# AD7606.net
KiCad netlist of a schematic drawn in Altium Designer
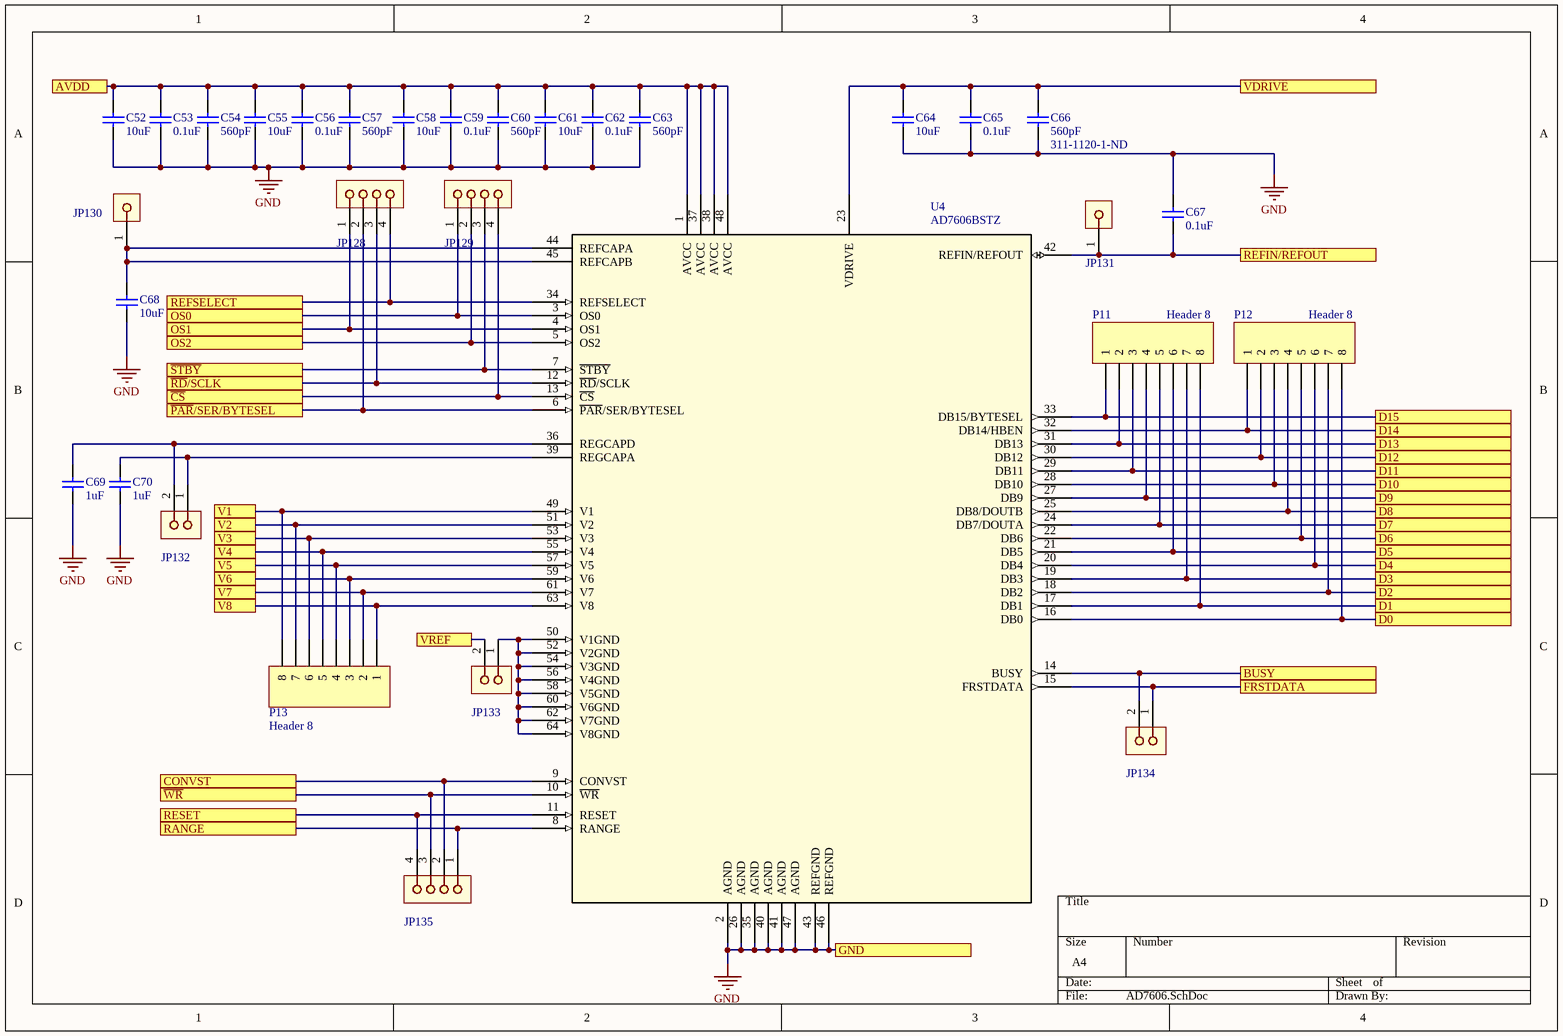
[diagram p0: AD7606.SchDoc]

(export (version "E")
  (design (tool "Eeschema 10.0.6"))
  (components
    (comp (ref "C52")
      (value "10uF")
      (footprint "CLS_Library:C0805")
      (description "Cap 10uF")
      (fields
        (field (name "MANUFACTURER") "Taiyo Yuden")
        (field (name "MANUFACTURER PART NUMBER") "UMK212SD103KD-T")
      )
      (libsource (lib "Chip1_TestBoard") (part "Cap 10uF"))
    )
    (comp (ref "C53")
      (value "0.1uF")
      (footprint "CLS_Library:C0805")
      (description "Cap 0.1uF")
      (fields
        (field (name "MANUFACTURER") "Taiyo Yuden")
        (field (name "MANUFACTURER PART NUMBER") "UMK212SD103KD-T")
      )
      (libsource (lib "Chip1_TestBoard") (part "Cap 0.1uF"))
    )
    (comp (ref "C54")
      (value "560pF")
      (footprint "CLS_Library:C0805")
      (description "Cap 560pF")
      (fields
        (field (name "MANUFACTURER") "Taiyo Yuden")
        (field (name "MANUFACTURER PART NUMBER") "UMK212SD103KD-T")
      )
      (libsource (lib "Chip1_TestBoard") (part "Cap 560pF"))
    )
    (comp (ref "C55")
      (value "10uF")
      (footprint "CLS_Library:C0805")
      (description "Cap 10uF")
      (fields
        (field (name "MANUFACTURER") "Taiyo Yuden")
        (field (name "MANUFACTURER PART NUMBER") "UMK212SD103KD-T")
      )
      (libsource (lib "Chip1_TestBoard") (part "Cap 10uF"))
    )
    (comp (ref "C56")
      (value "0.1uF")
      (footprint "CLS_Library:C0805")
      (description "Cap 0.1uF")
      (fields
        (field (name "MANUFACTURER") "Taiyo Yuden")
        (field (name "MANUFACTURER PART NUMBER") "UMK212SD103KD-T")
      )
      (libsource (lib "Chip1_TestBoard") (part "Cap 0.1uF"))
    )
    (comp (ref "C57")
      (value "560pF")
      (footprint "CLS_Library:C0805")
      (description "Cap 560pF")
      (fields
        (field (name "MANUFACTURER") "Taiyo Yuden")
        (field (name "MANUFACTURER PART NUMBER") "UMK212SD103KD-T")
      )
      (libsource (lib "Chip1_TestBoard") (part "Cap 560pF"))
    )
    (comp (ref "C58")
      (value "10uF")
      (footprint "CLS_Library:C0805")
      (description "Cap 10uF")
      (fields
        (field (name "MANUFACTURER") "Taiyo Yuden")
        (field (name "MANUFACTURER PART NUMBER") "UMK212SD103KD-T")
      )
      (libsource (lib "Chip1_TestBoard") (part "Cap 10uF"))
    )
    (comp (ref "C59")
      (value "0.1uF")
      (footprint "CLS_Library:C0805")
      (description "Cap 0.1uF")
      (fields
        (field (name "MANUFACTURER") "Taiyo Yuden")
        (field (name "MANUFACTURER PART NUMBER") "UMK212SD103KD-T")
      )
      (libsource (lib "Chip1_TestBoard") (part "Cap 0.1uF"))
    )
    (comp (ref "C60")
      (value "560pF")
      (footprint "CLS_Library:C0805")
      (description "Cap 560pF")
      (fields
        (field (name "MANUFACTURER") "Taiyo Yuden")
        (field (name "MANUFACTURER PART NUMBER") "UMK212SD103KD-T")
      )
      (libsource (lib "Chip1_TestBoard") (part "Cap 560pF"))
    )
    (comp (ref "C61")
      (value "10uF")
      (footprint "CLS_Library:C0805")
      (description "Cap 10uF")
      (fields
        (field (name "MANUFACTURER") "Taiyo Yuden")
        (field (name "MANUFACTURER PART NUMBER") "UMK212SD103KD-T")
      )
      (libsource (lib "Chip1_TestBoard") (part "Cap 10uF"))
    )
    (comp (ref "C62")
      (value "0.1uF")
      (footprint "CLS_Library:C0805")
      (description "Cap 0.1uF")
      (fields
        (field (name "MANUFACTURER") "Taiyo Yuden")
        (field (name "MANUFACTURER PART NUMBER") "UMK212SD103KD-T")
      )
      (libsource (lib "Chip1_TestBoard") (part "Cap 0.1uF"))
    )
    (comp (ref "C63")
      (value "560pF")
      (footprint "CLS_Library:C0805")
      (description "Cap 560pF")
      (fields
        (field (name "MANUFACTURER") "Taiyo Yuden")
        (field (name "MANUFACTURER PART NUMBER") "UMK212SD103KD-T")
      )
      (libsource (lib "Chip1_TestBoard") (part "Cap 560pF"))
    )
    (comp (ref "C64")
      (value "10uF")
      (footprint "CLS_Library:C0805")
      (description "Cap 10uF")
      (fields
        (field (name "MANUFACTURER") "Taiyo Yuden")
        (field (name "MANUFACTURER PART NUMBER") "UMK212SD103KD-T")
      )
      (libsource (lib "Chip1_TestBoard") (part "Cap 10uF"))
    )
    (comp (ref "C65")
      (value "0.1uF")
      (footprint "CLS_Library:C0805")
      (description "Cap 0.1uF")
      (fields
        (field (name "MANUFACTURER") "Taiyo Yuden")
        (field (name "MANUFACTURER PART NUMBER") "UMK212SD103KD-T")
      )
      (libsource (lib "Chip1_TestBoard") (part "Cap 0.1uF"))
    )
    (comp (ref "C66")
      (value "560pF")
      (footprint "CLS_Library:C0805")
      (description "Cap 560pF")
      (fields
        (field (name "MANUFACTURER") "Taiyo Yuden")
        (field (name "MANUFACTURER PART NUMBER") "UMK212SD103KD-T")
        (field (name "SUPPLIER PART NUMBER 1") "311-1120-1-ND")
      )
      (libsource (lib "Chip1_TestBoard") (part "Cap 560pF"))
    )
    (comp (ref "C67")
      (value "0.1uF")
      (footprint "CLS_Library:C0805")
      (description "Cap 0.1uF")
      (fields
        (field (name "MANUFACTURER") "Taiyo Yuden")
        (field (name "MANUFACTURER PART NUMBER") "UMK212SD103KD-T")
      )
      (libsource (lib "Chip1_TestBoard") (part "Cap 0.1uF"))
    )
    (comp (ref "C68")
      (value "10uF")
      (footprint "CLS_Library:C0805")
      (description "Cap 10uF")
      (fields
        (field (name "MANUFACTURER") "Taiyo Yuden")
        (field (name "MANUFACTURER PART NUMBER") "UMK212SD103KD-T")
      )
      (libsource (lib "Chip1_TestBoard") (part "Cap 10uF"))
    )
    (comp (ref "C69")
      (value "1uF")
      (footprint "CLS_Library:C0805")
      (description "Cap 1uF")
      (fields
        (field (name "MANUFACTURER") "Taiyo Yuden")
        (field (name "MANUFACTURER PART NUMBER") "UMK212SD103KD-T")
      )
      (libsource (lib "Chip1_TestBoard") (part "Cap 1uF"))
    )
    (comp (ref "C70")
      (value "1uF")
      (footprint "CLS_Library:C0805")
      (description "Cap 1uF")
      (fields
        (field (name "MANUFACTURER") "Taiyo Yuden")
        (field (name "MANUFACTURER PART NUMBER") "UMK212SD103KD-T")
      )
      (libsource (lib "Chip1_TestBoard") (part "Cap 1uF"))
    )
    (comp (ref "JP128")
      (value "01x04")
      (footprint "01x04_0.1in_th_straight_b_nom")
      (description "01X04 generic terminal connector")
      (libsource (lib "Chip1_TestBoard") (part "01x04"))
    )
    (comp (ref "JP129")
      (value "01x04")
      (footprint "01x04_0.1in_th_straight_b_nom")
      (description "01X04 generic terminal connector")
      (libsource (lib "Chip1_TestBoard") (part "01x04"))
    )
    (comp (ref "JP130")
      (value "01x01")
      (footprint "01x01_0_0.1in_th_straight_b_nom")
      (description "01X01 generic terminal connector")
      (libsource (lib "Chip1_TestBoard") (part "01x01"))
    )
    (comp (ref "JP131")
      (value "01x01")
      (footprint "01x01_0_0.1in_th_straight_b_nom")
      (description "01X01 generic terminal connector")
      (libsource (lib "Chip1_TestBoard") (part "01x01"))
    )
    (comp (ref "JP132")
      (value "01x02")
      (footprint "01x02_0.1in_th_straight_b_nom")
      (description "01X02 generic terminal connector")
      (libsource (lib "Chip1_TestBoard") (part "01x02"))
    )
    (comp (ref "JP133")
      (value "01x02")
      (footprint "01x02_0.1in_th_straight_b_nom")
      (description "01X02 generic terminal connector")
      (libsource (lib "Chip1_TestBoard") (part "01x02"))
    )
    (comp (ref "JP134")
      (value "01x02")
      (footprint "01x02_0.1in_th_straight_b_nom")
      (description "01X02 generic terminal connector")
      (libsource (lib "Chip1_TestBoard") (part "01x02"))
    )
    (comp (ref "JP135")
      (value "01x04")
      (footprint "01x04_0.1in_th_straight_b_nom")
      (description "01X04 generic terminal connector")
      (libsource (lib "") (part "01x04_1"))
    )
    (comp (ref "P11")
      (value "Header 8")
      (footprint "HDR1X8")
      (description "Header, 8-Pin")
      (fields (field (name "PUBLISHER") "Altium Limited"))
      (libsource (lib "Miscellaneous Connectors") (part "Header 8"))
    )
    (comp (ref "P12")
      (value "Header 8")
      (footprint "HDR1X8")
      (description "Header, 8-Pin")
      (fields (field (name "PUBLISHER") "Altium Limited"))
      (libsource (lib "Miscellaneous Connectors") (part "Header 8"))
    )
    (comp (ref "P13")
      (value "Header 8")
      (footprint "HDR1X8")
      (description "Header, 8-Pin")
      (fields (field (name "PUBLISHER") "Altium Limited"))
      (libsource (lib "") (part "Header 8_1"))
    )
    (comp (ref "U4")
      (value "AD7606BSTZ")
      (footprint "AD7606BSTZ")
      (description "No Description Available")
      (fields (field (name "COPYRIGHT") "Copyright (C) 2018 Accelerated Designs. All rights reserved"))
      (libsource (lib "Chip1_TestBoard") (part "AD7606BSTZ"))
    )
  )
  (nets
    (net (code "1") (name "/AVDD") (class "Default")
      (node (ref "C52") (pin "2") (pinfunction "2_2") (pintype "passive"))
      (node (ref "C53") (pin "2") (pinfunction "2_2") (pintype "passive"))
      (node (ref "C54") (pin "2") (pinfunction "2_2") (pintype "passive"))
      (node (ref "C55") (pin "2") (pinfunction "2_2") (pintype "passive"))
      (node (ref "C56") (pin "2") (pinfunction "2_2") (pintype "passive"))
      (node (ref "C57") (pin "2") (pinfunction "2_2") (pintype "passive"))
      (node (ref "C58") (pin "2") (pinfunction "2_2") (pintype "passive"))
      (node (ref "C59") (pin "2") (pinfunction "2_2") (pintype "passive"))
      (node (ref "C60") (pin "2") (pinfunction "2_2") (pintype "passive"))
      (node (ref "C61") (pin "2") (pinfunction "2_2") (pintype "passive"))
      (node (ref "C62") (pin "2") (pinfunction "2_2") (pintype "passive"))
      (node (ref "C63") (pin "2") (pinfunction "2_2") (pintype "passive"))
      (node (ref "U4") (pin "1") (pinfunction "AVCC_1") (pintype "power_in"))
      (node (ref "U4") (pin "37") (pinfunction "AVCC_37") (pintype "power_in"))
      (node (ref "U4") (pin "38") (pinfunction "AVCC_38") (pintype "power_in"))
      (node (ref "U4") (pin "48") (pinfunction "AVCC_48") (pintype "power_in"))
    )
    (net (code "2") (name "/BUSY") (class "Default")
      (node (ref "JP134") (pin "2") (pinfunction "2_2") (pintype "passive"))
      (node (ref "U4") (pin "14") (pinfunction "BUSY_14") (pintype "output"))
    )
    (net (code "3") (name "/CONVST") (class "Default")
      (node (ref "JP135") (pin "2") (pinfunction "2_2") (pintype "passive"))
      (node (ref "U4") (pin "9") (pinfunction "CONVST_9") (pintype "input"))
    )
    (net (code "4") (name "/D0") (class "Default")
      (node (ref "P12") (pin "8") (pinfunction "8_8") (pintype "passive"))
      (node (ref "U4") (pin "16") (pinfunction "DB0_16") (pintype "output"))
    )
    (net (code "5") (name "/D1") (class "Default")
      (node (ref "P11") (pin "8") (pinfunction "8_8") (pintype "passive"))
      (node (ref "U4") (pin "17") (pinfunction "DB1_17") (pintype "output"))
    )
    (net (code "6") (name "/D2") (class "Default")
      (node (ref "P12") (pin "7") (pinfunction "7_7") (pintype "passive"))
      (node (ref "U4") (pin "18") (pinfunction "DB2_18") (pintype "output"))
    )
    (net (code "7") (name "/D3") (class "Default")
      (node (ref "P11") (pin "7") (pinfunction "7_7") (pintype "passive"))
      (node (ref "U4") (pin "19") (pinfunction "DB3_19") (pintype "output"))
    )
    (net (code "8") (name "/D4") (class "Default")
      (node (ref "P12") (pin "6") (pinfunction "6_6") (pintype "passive"))
      (node (ref "U4") (pin "20") (pinfunction "DB4_20") (pintype "output"))
    )
    (net (code "9") (name "/D5") (class "Default")
      (node (ref "P11") (pin "6") (pinfunction "6_6") (pintype "passive"))
      (node (ref "U4") (pin "21") (pinfunction "DB5_21") (pintype "output"))
    )
    (net (code "10") (name "/D6") (class "Default")
      (node (ref "P12") (pin "5") (pinfunction "5_5") (pintype "passive"))
      (node (ref "U4") (pin "22") (pinfunction "DB6_22") (pintype "output"))
    )
    (net (code "11") (name "/D7") (class "Default")
      (node (ref "P11") (pin "5") (pinfunction "5_5") (pintype "passive"))
      (node (ref "U4") (pin "24") (pinfunction "DB7/DOUTA_24") (pintype "output"))
    )
    (net (code "12") (name "/D8") (class "Default")
      (node (ref "P12") (pin "4") (pinfunction "4_4") (pintype "passive"))
      (node (ref "U4") (pin "25") (pinfunction "DB8/DOUTB_25") (pintype "output"))
    )
    (net (code "13") (name "/D9") (class "Default")
      (node (ref "P11") (pin "4") (pinfunction "4_4") (pintype "passive"))
      (node (ref "U4") (pin "27") (pinfunction "DB9_27") (pintype "output"))
    )
    (net (code "14") (name "/D10") (class "Default")
      (node (ref "P12") (pin "3") (pinfunction "3_3") (pintype "passive"))
      (node (ref "U4") (pin "28") (pinfunction "DB10_28") (pintype "output"))
    )
    (net (code "15") (name "/D11") (class "Default")
      (node (ref "P11") (pin "3") (pinfunction "3_3") (pintype "passive"))
      (node (ref "U4") (pin "29") (pinfunction "DB11_29") (pintype "output"))
    )
    (net (code "16") (name "/D12") (class "Default")
      (node (ref "P12") (pin "2") (pinfunction "2_2") (pintype "passive"))
      (node (ref "U4") (pin "30") (pinfunction "DB12_30") (pintype "output"))
    )
    (net (code "17") (name "/D13") (class "Default")
      (node (ref "P11") (pin "2") (pinfunction "2_2") (pintype "passive"))
      (node (ref "U4") (pin "31") (pinfunction "DB13_31") (pintype "output"))
    )
    (net (code "18") (name "/D14") (class "Default")
      (node (ref "P12") (pin "1") (pinfunction "1_1") (pintype "passive"))
      (node (ref "U4") (pin "32") (pinfunction "DB14/HBEN_32") (pintype "output"))
    )
    (net (code "19") (name "/D15") (class "Default")
      (node (ref "P11") (pin "1") (pinfunction "1_1") (pintype "passive"))
      (node (ref "U4") (pin "33") (pinfunction "DB15/BYTESEL_33") (pintype "output"))
    )
    (net (code "20") (name "/FRSTDATA") (class "Default")
      (node (ref "JP134") (pin "1") (pinfunction "1_1") (pintype "passive"))
      (node (ref "U4") (pin "15") (pinfunction "FRSTDATA_15") (pintype "output"))
    )
    (net (code "21") (name "/OS0") (class "Default")
      (node (ref "JP129") (pin "1") (pinfunction "1_1") (pintype "passive"))
      (node (ref "U4") (pin "3") (pinfunction "OS0_3") (pintype "input"))
    )
    (net (code "22") (name "/OS1") (class "Default")
      (node (ref "JP128") (pin "1") (pinfunction "1_1") (pintype "passive"))
      (node (ref "U4") (pin "4") (pinfunction "OS1_4") (pintype "input"))
    )
    (net (code "23") (name "/OS2") (class "Default")
      (node (ref "JP129") (pin "2") (pinfunction "2_2") (pintype "passive"))
      (node (ref "U4") (pin "5") (pinfunction "OS2_5") (pintype "input"))
    )
    (net (code "24") (name "/RANGE") (class "Default")
      (node (ref "JP135") (pin "1") (pinfunction "1_1") (pintype "passive"))
      (node (ref "U4") (pin "8") (pinfunction "RANGE_8") (pintype "input"))
    )
    (net (code "25") (name "/REFIN{slash}REFOUT") (class "Default")
      (node (ref "C67") (pin "1") (pinfunction "1_1") (pintype "passive"))
      (node (ref "JP131") (pin "1") (pinfunction "1_1") (pintype "passive"))
      (node (ref "U4") (pin "42") (pinfunction "REFIN/REFOUT_42") (pintype "bidirectional"))
    )
    (net (code "26") (name "/REFSELECT") (class "Default")
      (node (ref "JP128") (pin "4") (pinfunction "4_4") (pintype "passive"))
      (node (ref "U4") (pin "34") (pinfunction "REFSELECT_34") (pintype "input"))
    )
    (net (code "27") (name "/RESET") (class "Default")
      (node (ref "JP135") (pin "4") (pinfunction "4_4") (pintype "passive"))
      (node (ref "U4") (pin "11") (pinfunction "RESET_11") (pintype "input"))
    )
    (net (code "28") (name "/V1") (class "Default")
      (node (ref "P13") (pin "8") (pinfunction "8_8") (pintype "passive"))
      (node (ref "U4") (pin "49") (pinfunction "V1_49") (pintype "input"))
    )
    (net (code "29") (name "/V2") (class "Default")
      (node (ref "P13") (pin "7") (pinfunction "7_7") (pintype "passive"))
      (node (ref "U4") (pin "51") (pinfunction "V2_51") (pintype "input"))
    )
    (net (code "30") (name "/V3") (class "Default")
      (node (ref "P13") (pin "6") (pinfunction "6_6") (pintype "passive"))
      (node (ref "U4") (pin "53") (pinfunction "V3_53") (pintype "input"))
    )
    (net (code "31") (name "/V4") (class "Default")
      (node (ref "P13") (pin "5") (pinfunction "5_5") (pintype "passive"))
      (node (ref "U4") (pin "55") (pinfunction "V4_55") (pintype "input"))
    )
    (net (code "32") (name "/V5") (class "Default")
      (node (ref "P13") (pin "4") (pinfunction "4_4") (pintype "passive"))
      (node (ref "U4") (pin "57") (pinfunction "V5_57") (pintype "input"))
    )
    (net (code "33") (name "/V6") (class "Default")
      (node (ref "P13") (pin "3") (pinfunction "3_3") (pintype "passive"))
      (node (ref "U4") (pin "59") (pinfunction "V6_59") (pintype "input"))
    )
    (net (code "34") (name "/V7") (class "Default")
      (node (ref "P13") (pin "2") (pinfunction "2_2") (pintype "passive"))
      (node (ref "U4") (pin "61") (pinfunction "V7_61") (pintype "input"))
    )
    (net (code "35") (name "/V8") (class "Default")
      (node (ref "P13") (pin "1") (pinfunction "1_1") (pintype "passive"))
      (node (ref "U4") (pin "63") (pinfunction "V8_63") (pintype "input"))
    )
    (net (code "36") (name "/VDRIVE") (class "Default")
      (node (ref "C64") (pin "2") (pinfunction "2_2") (pintype "passive"))
      (node (ref "C65") (pin "2") (pinfunction "2_2") (pintype "passive"))
      (node (ref "C66") (pin "2") (pinfunction "2_2") (pintype "passive"))
      (node (ref "U4") (pin "23") (pinfunction "VDRIVE_23") (pintype "power_in"))
    )
    (net (code "37") (name "/VREF") (class "Default")
      (node (ref "JP133") (pin "2") (pinfunction "2_2") (pintype "passive"))
    )
    (net (code "38") (name "/~{CS}") (class "Default")
      (node (ref "JP129") (pin "4") (pinfunction "4_4") (pintype "passive"))
      (node (ref "U4") (pin "13") (pinfunction "~{CS}_13") (pintype "input"))
    )
    (net (code "39") (name "/~{PAR}{slash}SER{slash}BYTESEL") (class "Default")
      (node (ref "JP128") (pin "2") (pinfunction "2_2") (pintype "passive"))
      (node (ref "U4") (pin "6") (pinfunction "~{PAR}/SER/BYTESEL_6") (pintype "input"))
    )
    (net (code "40") (name "/~{RD}{slash}SCLK") (class "Default")
      (node (ref "JP128") (pin "3") (pinfunction "3_3") (pintype "passive"))
      (node (ref "U4") (pin "12") (pinfunction "~{RD}/SCLK_12") (pintype "input"))
    )
    (net (code "41") (name "/~{STBY}") (class "Default")
      (node (ref "JP129") (pin "3") (pinfunction "3_3") (pintype "passive"))
      (node (ref "U4") (pin "7") (pinfunction "~{STBY}_7") (pintype "input"))
    )
    (net (code "42") (name "/~{WR}") (class "Default")
      (node (ref "JP135") (pin "3") (pinfunction "3_3") (pintype "passive"))
      (node (ref "U4") (pin "10") (pinfunction "~{WR}_10") (pintype "input"))
    )
    (net (code "43") (name "GND") (class "Default")
      (node (ref "C52") (pin "1") (pinfunction "1_1") (pintype "passive"))
      (node (ref "C53") (pin "1") (pinfunction "1_1") (pintype "passive"))
      (node (ref "C54") (pin "1") (pinfunction "1_1") (pintype "passive"))
      (node (ref "C55") (pin "1") (pinfunction "1_1") (pintype "passive"))
      (node (ref "C56") (pin "1") (pinfunction "1_1") (pintype "passive"))
      (node (ref "C57") (pin "1") (pinfunction "1_1") (pintype "passive"))
      (node (ref "C58") (pin "1") (pinfunction "1_1") (pintype "passive"))
      (node (ref "C59") (pin "1") (pinfunction "1_1") (pintype "passive"))
      (node (ref "C60") (pin "1") (pinfunction "1_1") (pintype "passive"))
      (node (ref "C61") (pin "1") (pinfunction "1_1") (pintype "passive"))
      (node (ref "C62") (pin "1") (pinfunction "1_1") (pintype "passive"))
      (node (ref "C63") (pin "1") (pinfunction "1_1") (pintype "passive"))
      (node (ref "C64") (pin "1") (pinfunction "1_1") (pintype "passive"))
      (node (ref "C65") (pin "1") (pinfunction "1_1") (pintype "passive"))
      (node (ref "C66") (pin "1") (pinfunction "1_1") (pintype "passive"))
      (node (ref "C67") (pin "2") (pinfunction "2_2") (pintype "passive"))
      (node (ref "C68") (pin "1") (pinfunction "1_1") (pintype "passive"))
      (node (ref "C69") (pin "1") (pinfunction "1_1") (pintype "passive"))
      (node (ref "C70") (pin "1") (pinfunction "1_1") (pintype "passive"))
      (node (ref "U4") (pin "2") (pinfunction "AGND_2") (pintype "power_in"))
      (node (ref "U4") (pin "26") (pinfunction "AGND_26") (pintype "power_in"))
      (node (ref "U4") (pin "35") (pinfunction "AGND_35") (pintype "power_in"))
      (node (ref "U4") (pin "40") (pinfunction "AGND_40") (pintype "power_in"))
      (node (ref "U4") (pin "41") (pinfunction "AGND_41") (pintype "power_in"))
      (node (ref "U4") (pin "43") (pinfunction "REFGND_43") (pintype "power_in"))
      (node (ref "U4") (pin "46") (pinfunction "REFGND_46") (pintype "power_in"))
      (node (ref "U4") (pin "47") (pinfunction "AGND_47") (pintype "power_in"))
    )
    (net (code "44") (name "Net-(U4-REFCAPA)") (class "Default")
      (node (ref "C68") (pin "2") (pinfunction "2_2") (pintype "passive"))
      (node (ref "JP130") (pin "1") (pinfunction "1_1") (pintype "passive"))
      (node (ref "U4") (pin "44") (pinfunction "REFCAPA_44") (pintype "passive"))
      (node (ref "U4") (pin "45") (pinfunction "REFCAPB_45") (pintype "passive"))
    )
    (net (code "45") (name "Net-(U4-REGCAPA)") (class "Default")
      (node (ref "C70") (pin "2") (pinfunction "2_2") (pintype "passive"))
      (node (ref "JP132") (pin "1") (pinfunction "1_1") (pintype "passive"))
      (node (ref "U4") (pin "39") (pinfunction "REGCAPA_39") (pintype "passive"))
    )
    (net (code "46") (name "Net-(U4-REGCAPD)") (class "Default")
      (node (ref "C69") (pin "2") (pinfunction "2_2") (pintype "passive"))
      (node (ref "JP132") (pin "2") (pinfunction "2_2") (pintype "passive"))
      (node (ref "U4") (pin "36") (pinfunction "REGCAPD_36") (pintype "passive"))
    )
    (net (code "47") (name "Net-(U4-V1GND)") (class "Default")
      (node (ref "JP133") (pin "1") (pinfunction "1_1") (pintype "passive"))
      (node (ref "U4") (pin "50") (pinfunction "V1GND_50") (pintype "input"))
      (node (ref "U4") (pin "52") (pinfunction "V2GND_52") (pintype "input"))
      (node (ref "U4") (pin "54") (pinfunction "V3GND_54") (pintype "input"))
      (node (ref "U4") (pin "56") (pinfunction "V4GND_56") (pintype "input"))
      (node (ref "U4") (pin "58") (pinfunction "V5GND_58") (pintype "input"))
      (node (ref "U4") (pin "60") (pinfunction "V6GND_60") (pintype "input"))
      (node (ref "U4") (pin "62") (pinfunction "V7GND_62") (pintype "input"))
      (node (ref "U4") (pin "64") (pinfunction "V8GND_64") (pintype "input"))
    )
  )
)
